# WemosD1_MOIST.net
KiCad netlist of a schematic drawn in EAGLE
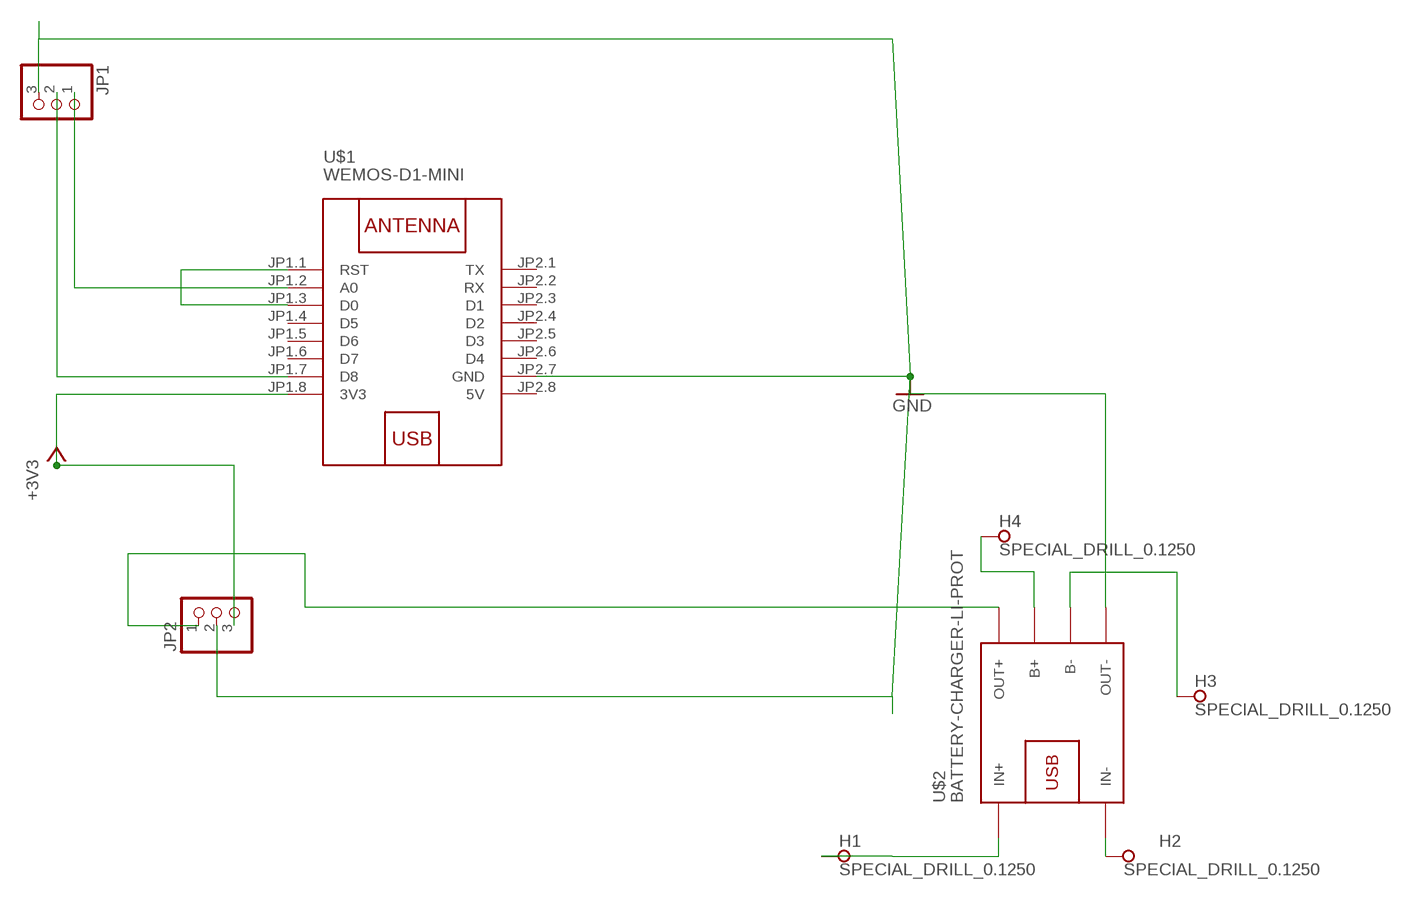
[diagram p0: schematic, sheet 1]

(export (version "E")
  (design (tool "Eeschema 10.0.6"))
  (components
    (comp (ref "H1")
      (value "SPECIAL_DRILL_0.1250")
      (footprint "eagle-import:PAD_0.1250")
      (libsource (lib "eagle-import") (part "SPECIAL_DRILL_0.1250"))
    )
    (comp (ref "H2")
      (value "SPECIAL_DRILL_0.1250")
      (footprint "eagle-import:PAD_0.1250")
      (libsource (lib "eagle-import") (part "SPECIAL_DRILL_0.1250"))
    )
    (comp (ref "H3")
      (value "SPECIAL_DRILL_0.1250")
      (footprint "eagle-import:PAD_0.1250")
      (libsource (lib "eagle-import") (part "SPECIAL_DRILL_0.1250"))
    )
    (comp (ref "H4")
      (value "SPECIAL_DRILL_0.1250")
      (footprint "eagle-import:PAD_0.1250")
      (libsource (lib "eagle-import") (part "SPECIAL_DRILL_0.1250"))
    )
    (comp (ref "JP1")
      (value "PINHD-1X3/90")
      (footprint "eagle-import:1X03_90")
      (libsource (lib "eagle-import") (part "PINHD-1X3/90"))
    )
    (comp (ref "JP2")
      (value "PINHD-1X3/90")
      (footprint "eagle-import:1X03_90")
      (libsource (lib "eagle-import") (part "PINHD-1X3/90"))
    )
    (comp (ref "U$1")
      (value "WEMOS-D1-MINI")
      (footprint "eagle-import:WEMOS-D1-MINI")
      (libsource (lib "eagle-import") (part "WEMOS-D1-MINI"))
    )
    (comp (ref "U$2")
      (value "BATTERY-CHARGER-LI-PROT")
      (footprint "eagle-import:BATTERY-CHARGER-LI-PROT")
      (libsource (lib "eagle-import") (part "BATTERY-CHARGER-LI-PROT"))
    )
  )
  (nets
    (net (code "1") (name "+3V3") (class "Default")
      (node (ref "JP2") (pin "3") (pinfunction "3_3") (pintype "passive"))
      (node (ref "U$1") (pin "JP1.8") (pinfunction "3V3_JP1.8") (pintype "power_in"))
    )
    (net (code "2") (name "/5V") (class "Default")
      (node (ref "U$1") (pin "JP2.8") (pinfunction "5V_JP2.8") (pintype "power_in"))
    )
    (net (code "3") (name "GND") (class "Default")
      (node (ref "JP1") (pin "3") (pinfunction "3_3") (pintype "passive"))
      (node (ref "JP2") (pin "2") (pinfunction "2_2") (pintype "passive"))
      (node (ref "U$1") (pin "JP2.7") (pinfunction "GND_JP2.7") (pintype "power_in"))
      (node (ref "U$2") (pin "OUT-") (pinfunction "OUT-_OUT-") (pintype "bidirectional"))
    )
    (net (code "4") (name "Net-(H1-Pad1)") (class "Default")
      (node (ref "H1") (pin "1") (pinfunction "1_1") (pintype "passive"))
      (node (ref "U$2") (pin "IN+") (pinfunction "IN+_IN+") (pintype "bidirectional"))
    )
    (net (code "5") (name "Net-(H2-Pad1)") (class "Default")
      (node (ref "H2") (pin "1") (pinfunction "1_1") (pintype "passive"))
      (node (ref "U$2") (pin "IN-") (pinfunction "IN-_IN-") (pintype "bidirectional"))
    )
    (net (code "6") (name "Net-(H3-Pad1)") (class "Default")
      (node (ref "H3") (pin "1") (pinfunction "1_1") (pintype "passive"))
      (node (ref "U$2") (pin "B-") (pinfunction "B-_B-") (pintype "bidirectional"))
    )
    (net (code "7") (name "Net-(H4-Pad1)") (class "Default")
      (node (ref "H4") (pin "1") (pinfunction "1_1") (pintype "passive"))
      (node (ref "U$2") (pin "B+") (pinfunction "B+_B+") (pintype "bidirectional"))
    )
    (net (code "8") (name "Net-(JP2-Pad1)") (class "Default")
      (node (ref "JP2") (pin "1") (pinfunction "1_1") (pintype "passive"))
      (node (ref "U$2") (pin "OUT+") (pinfunction "OUT+_OUT+") (pintype "bidirectional"))
    )
    (net (code "9") (name "Net-(U$1-A0)") (class "Default")
      (node (ref "JP1") (pin "1") (pinfunction "1_1") (pintype "passive"))
      (node (ref "U$1") (pin "JP1.2") (pinfunction "A0_JP1.2") (pintype "bidirectional"))
    )
    (net (code "10") (name "Net-(U$1-D0)") (class "Default")
      (node (ref "U$1") (pin "JP1.1") (pinfunction "RST_JP1.1") (pintype "bidirectional"))
      (node (ref "U$1") (pin "JP1.3") (pinfunction "D0_JP1.3") (pintype "bidirectional"))
    )
    (net (code "11") (name "Net-(U$1-D8)") (class "Default")
      (node (ref "JP1") (pin "2") (pinfunction "2_2") (pintype "passive"))
      (node (ref "U$1") (pin "JP1.7") (pinfunction "D8_JP1.7") (pintype "bidirectional"))
    )
    (net (code "12") (name "unconnected-(U$1-D1-PadJP2.3)") (class "Default")
      (node (ref "U$1") (pin "JP2.3") (pinfunction "D1_JP2.3") (pintype "bidirectional"))
    )
    (net (code "13") (name "unconnected-(U$1-D2-PadJP2.4)") (class "Default")
      (node (ref "U$1") (pin "JP2.4") (pinfunction "D2_JP2.4") (pintype "bidirectional"))
    )
    (net (code "14") (name "unconnected-(U$1-D3-PadJP2.5)") (class "Default")
      (node (ref "U$1") (pin "JP2.5") (pinfunction "D3_JP2.5") (pintype "bidirectional"))
    )
    (net (code "15") (name "unconnected-(U$1-D4-PadJP2.6)") (class "Default")
      (node (ref "U$1") (pin "JP2.6") (pinfunction "D4_JP2.6") (pintype "bidirectional"))
    )
    (net (code "16") (name "unconnected-(U$1-D5-PadJP1.4)") (class "Default")
      (node (ref "U$1") (pin "JP1.4") (pinfunction "D5_JP1.4") (pintype "bidirectional"))
    )
    (net (code "17") (name "unconnected-(U$1-D6-PadJP1.5)") (class "Default")
      (node (ref "U$1") (pin "JP1.5") (pinfunction "D6_JP1.5") (pintype "bidirectional"))
    )
    (net (code "18") (name "unconnected-(U$1-D7-PadJP1.6)") (class "Default")
      (node (ref "U$1") (pin "JP1.6") (pinfunction "D7_JP1.6") (pintype "bidirectional"))
    )
    (net (code "19") (name "unconnected-(U$1-RX-PadJP2.2)") (class "Default")
      (node (ref "U$1") (pin "JP2.2") (pinfunction "RX_JP2.2") (pintype "bidirectional"))
    )
    (net (code "20") (name "unconnected-(U$1-TX-PadJP2.1)") (class "Default")
      (node (ref "U$1") (pin "JP2.1") (pinfunction "TX_JP2.1") (pintype "bidirectional"))
    )
  )
)
